# Banker_EDGE_2_DSUB.net
KiCad netlist of a schematic drawn in Altium Designer
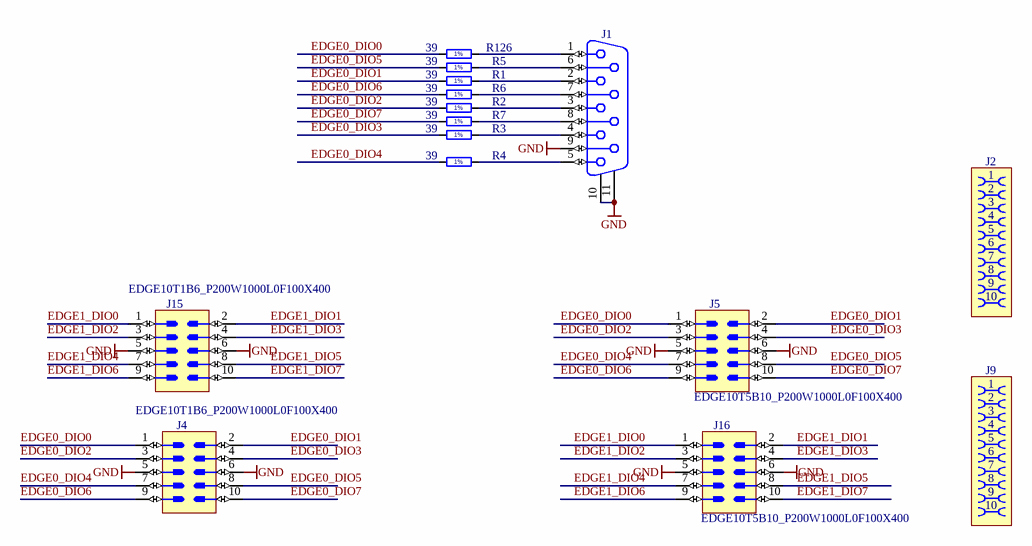
[diagram p0: Banker_EDGE_2_DSUB.SchDoc]

(export (version "E")
  (design (tool "Eeschema 10.0.6"))
  (components
    (comp (ref "J1")
      (value "D-Sub")
      (footprint "AMPHENOL_L77SDEH09SOL2RM5")
      (description "Connector D-sub 9 Female")
      (fields
        (field (name "PART NUMBER") "AMPHENOL_L77SDEH09SOL2RM5")
        (field (name "MANUFACTURER") "AMPHENOL")
        (field (name "AUTHOR") "CERN DEM JLC")
      )
      (libsource (lib "Connectors") (part "Connector D-sub 9 Female"))
    )
    (comp (ref "J2")
      (value "~")
      (footprint "AVX_00 9159 010 061 916")
      (description "Open Ended Card Edge Connector, 9159 Series")
      (fields
        (field (name "PART NUMBER") "AVX_00 9159 010 061 916")
        (field (name "MANUFACTURER") "AVX")
        (field (name "AUTHOR") "CERN DEM MR")
      )
      (libsource (lib "Connectors") (part "AVX_00 9159 010 061 916"))
    )
    (comp (ref "J4")
      (value "~")
      (footprint "EDGE10T1B6_P200W1000L0F100X400")
      (description "PCB Edge Connector 10 (2x5)")
      (fields
        (field (name "PART NUMBER") "EDGE10T1B6_P200W1000L0F100X400")
        (field (name "AUTHOR") "CERN DEM MR")
      )
      (libsource (lib "Connectors") (part "PCB Edge Connector 10 (2x5)"))
    )
    (comp (ref "J5")
      (value "~")
      (footprint "EDGE10T5B10_P200W1000L0F100X400")
      (description "PCB Edge Connector 10 (2x5)")
      (fields
        (field (name "PART NUMBER") "EDGE10T5B10_P200W1000L0F100X400")
        (field (name "AUTHOR") "CERN DEM MR")
      )
      (libsource (lib "Connectors") (part "PCB Edge Connector 10 (2x5)"))
    )
    (comp (ref "J9")
      (value "~")
      (footprint "AVX_00 9159 010 061 916")
      (description "Open Ended Card Edge Connector, 9159 Series")
      (fields
        (field (name "PART NUMBER") "AVX_00 9159 010 061 916")
        (field (name "MANUFACTURER") "AVX")
        (field (name "AUTHOR") "CERN DEM MR")
      )
      (libsource (lib "Connectors") (part "AVX_00 9159 010 061 916"))
    )
    (comp (ref "J15")
      (value "~")
      (footprint "EDGE10T1B6_P200W1000L0F100X400")
      (description "PCB Edge Connector 10 (2x5)")
      (fields
        (field (name "PART NUMBER") "EDGE10T1B6_P200W1000L0F100X400")
        (field (name "AUTHOR") "CERN DEM MR")
      )
      (libsource (lib "Connectors") (part "PCB Edge Connector 10 (2x5)"))
    )
    (comp (ref "J16")
      (value "~")
      (footprint "EDGE10T5B10_P200W1000L0F100X400")
      (description "PCB Edge Connector 10 (2x5)")
      (fields
        (field (name "PART NUMBER") "EDGE10T5B10_P200W1000L0F100X400")
        (field (name "AUTHOR") "CERN DEM MR")
      )
      (libsource (lib "Connectors") (part "PCB Edge Connector 10 (2x5)"))
    )
    (comp (ref "R1")
      (value "39")
      (footprint "RESC2012X60N")
      (description "Resistor - 1%")
      (fields
        (field (name "PART NUMBER") "R0805_39R_1%_0.125W_100PPM")
        (field (name "POWER") "0.125W")
        (field (name "AUTHOR") "CERN DEM JLC")
      )
      (libsource (lib "Resistors") (part "Resistor - 1%"))
    )
    (comp (ref "R2")
      (value "39")
      (footprint "RESC2012X60N")
      (description "Resistor - 1%")
      (fields
        (field (name "PART NUMBER") "R0805_39R_1%_0.125W_100PPM")
        (field (name "POWER") "0.125W")
        (field (name "AUTHOR") "CERN DEM JLC")
      )
      (libsource (lib "Resistors") (part "Resistor - 1%"))
    )
    (comp (ref "R3")
      (value "39")
      (footprint "RESC2012X60N")
      (description "Resistor - 1%")
      (fields
        (field (name "PART NUMBER") "R0805_39R_1%_0.125W_100PPM")
        (field (name "POWER") "0.125W")
        (field (name "AUTHOR") "CERN DEM JLC")
      )
      (libsource (lib "Resistors") (part "Resistor - 1%"))
    )
    (comp (ref "R4")
      (value "39")
      (footprint "RESC2012X60N")
      (description "Resistor - 1%")
      (fields
        (field (name "PART NUMBER") "R0805_39R_1%_0.125W_100PPM")
        (field (name "POWER") "0.125W")
        (field (name "AUTHOR") "CERN DEM JLC")
      )
      (libsource (lib "Resistors") (part "Resistor - 1%"))
    )
    (comp (ref "R5")
      (value "39")
      (footprint "RESC2012X60N")
      (description "Resistor - 1%")
      (fields
        (field (name "PART NUMBER") "R0805_39R_1%_0.125W_100PPM")
        (field (name "POWER") "0.125W")
        (field (name "AUTHOR") "CERN DEM JLC")
      )
      (libsource (lib "Resistors") (part "Resistor - 1%"))
    )
    (comp (ref "R6")
      (value "39")
      (footprint "RESC2012X60N")
      (description "Resistor - 1%")
      (fields
        (field (name "PART NUMBER") "R0805_39R_1%_0.125W_100PPM")
        (field (name "POWER") "0.125W")
        (field (name "AUTHOR") "CERN DEM JLC")
      )
      (libsource (lib "Resistors") (part "Resistor - 1%"))
    )
    (comp (ref "R7")
      (value "39")
      (footprint "RESC2012X60N")
      (description "Resistor - 1%")
      (fields
        (field (name "PART NUMBER") "R0805_39R_1%_0.125W_100PPM")
        (field (name "POWER") "0.125W")
        (field (name "AUTHOR") "CERN DEM JLC")
      )
      (libsource (lib "Resistors") (part "Resistor - 1%"))
    )
    (comp (ref "R126")
      (value "39")
      (footprint "RESC2012X60N")
      (description "Resistor - 1%")
      (fields
        (field (name "PART NUMBER") "R0805_39R_1%_0.125W_100PPM")
        (field (name "POWER") "0.125W")
        (field (name "AUTHOR") "CERN DEM JLC")
      )
      (libsource (lib "Resistors") (part "Resistor - 1%"))
    )
  )
  (nets
    (net (code "1") (name "/EDGE0_DIO0") (class "Default")
      (node (ref "J4") (pin "1") (pinfunction "1_1") (pintype "bidirectional"))
      (node (ref "J5") (pin "1") (pinfunction "1_1") (pintype "bidirectional"))
      (node (ref "R126") (pin "1") (pinfunction "1_1") (pintype "passive"))
    )
    (net (code "2") (name "/EDGE0_DIO1") (class "Default")
      (node (ref "J4") (pin "2") (pinfunction "2_2") (pintype "bidirectional"))
      (node (ref "J5") (pin "2") (pinfunction "2_2") (pintype "bidirectional"))
      (node (ref "R1") (pin "1") (pinfunction "1_1") (pintype "passive"))
    )
    (net (code "3") (name "/EDGE0_DIO2") (class "Default")
      (node (ref "J4") (pin "3") (pinfunction "3_3") (pintype "bidirectional"))
      (node (ref "J5") (pin "3") (pinfunction "3_3") (pintype "bidirectional"))
      (node (ref "R2") (pin "1") (pinfunction "1_1") (pintype "passive"))
    )
    (net (code "4") (name "/EDGE0_DIO3") (class "Default")
      (node (ref "J4") (pin "4") (pinfunction "4_4") (pintype "bidirectional"))
      (node (ref "J5") (pin "4") (pinfunction "4_4") (pintype "bidirectional"))
      (node (ref "R3") (pin "1") (pinfunction "1_1") (pintype "passive"))
    )
    (net (code "5") (name "/EDGE0_DIO4") (class "Default")
      (node (ref "J4") (pin "7") (pinfunction "7_7") (pintype "bidirectional"))
      (node (ref "J5") (pin "7") (pinfunction "7_7") (pintype "bidirectional"))
      (node (ref "R4") (pin "1") (pinfunction "1_1") (pintype "passive"))
    )
    (net (code "6") (name "/EDGE0_DIO5") (class "Default")
      (node (ref "J4") (pin "8") (pinfunction "8_8") (pintype "bidirectional"))
      (node (ref "J5") (pin "8") (pinfunction "8_8") (pintype "bidirectional"))
      (node (ref "R5") (pin "1") (pinfunction "1_1") (pintype "passive"))
    )
    (net (code "7") (name "/EDGE0_DIO6") (class "Default")
      (node (ref "J4") (pin "9") (pinfunction "9_9") (pintype "bidirectional"))
      (node (ref "J5") (pin "9") (pinfunction "9_9") (pintype "bidirectional"))
      (node (ref "R6") (pin "1") (pinfunction "1_1") (pintype "passive"))
    )
    (net (code "8") (name "/EDGE0_DIO7") (class "Default")
      (node (ref "J4") (pin "10") (pinfunction "10_10") (pintype "bidirectional"))
      (node (ref "J5") (pin "10") (pinfunction "10_10") (pintype "bidirectional"))
      (node (ref "R7") (pin "1") (pinfunction "1_1") (pintype "passive"))
    )
    (net (code "9") (name "/EDGE1_DIO0") (class "Default")
      (node (ref "J15") (pin "1") (pinfunction "1_1") (pintype "bidirectional"))
      (node (ref "J16") (pin "1") (pinfunction "1_1") (pintype "bidirectional"))
    )
    (net (code "10") (name "/EDGE1_DIO1") (class "Default")
      (node (ref "J15") (pin "2") (pinfunction "2_2") (pintype "bidirectional"))
      (node (ref "J16") (pin "2") (pinfunction "2_2") (pintype "bidirectional"))
    )
    (net (code "11") (name "/EDGE1_DIO2") (class "Default")
      (node (ref "J15") (pin "3") (pinfunction "3_3") (pintype "bidirectional"))
      (node (ref "J16") (pin "3") (pinfunction "3_3") (pintype "bidirectional"))
    )
    (net (code "12") (name "/EDGE1_DIO3") (class "Default")
      (node (ref "J15") (pin "4") (pinfunction "4_4") (pintype "bidirectional"))
      (node (ref "J16") (pin "4") (pinfunction "4_4") (pintype "bidirectional"))
    )
    (net (code "13") (name "/EDGE1_DIO4") (class "Default")
      (node (ref "J15") (pin "7") (pinfunction "7_7") (pintype "bidirectional"))
      (node (ref "J16") (pin "7") (pinfunction "7_7") (pintype "bidirectional"))
    )
    (net (code "14") (name "/EDGE1_DIO5") (class "Default")
      (node (ref "J15") (pin "8") (pinfunction "8_8") (pintype "bidirectional"))
      (node (ref "J16") (pin "8") (pinfunction "8_8") (pintype "bidirectional"))
    )
    (net (code "15") (name "/EDGE1_DIO6") (class "Default")
      (node (ref "J15") (pin "9") (pinfunction "9_9") (pintype "bidirectional"))
      (node (ref "J16") (pin "9") (pinfunction "9_9") (pintype "bidirectional"))
    )
    (net (code "16") (name "/EDGE1_DIO7") (class "Default")
      (node (ref "J15") (pin "10") (pinfunction "10_10") (pintype "bidirectional"))
      (node (ref "J16") (pin "10") (pinfunction "10_10") (pintype "bidirectional"))
    )
    (net (code "17") (name "GND") (class "Default")
      (node (ref "J1") (pin "10") (pinfunction "10_10") (pintype "passive"))
      (node (ref "J1") (pin "11") (pinfunction "11_11") (pintype "passive"))
      (node (ref "J1") (pin "9") (pinfunction "9_9") (pintype "bidirectional"))
      (node (ref "J15") (pin "5") (pinfunction "5_5") (pintype "bidirectional"))
      (node (ref "J15") (pin "6") (pinfunction "6_6") (pintype "bidirectional"))
      (node (ref "J16") (pin "5") (pinfunction "5_5") (pintype "bidirectional"))
      (node (ref "J16") (pin "6") (pinfunction "6_6") (pintype "bidirectional"))
      (node (ref "J4") (pin "5") (pinfunction "5_5") (pintype "bidirectional"))
      (node (ref "J4") (pin "6") (pinfunction "6_6") (pintype "bidirectional"))
      (node (ref "J5") (pin "5") (pinfunction "5_5") (pintype "bidirectional"))
      (node (ref "J5") (pin "6") (pinfunction "6_6") (pintype "bidirectional"))
    )
    (net (code "18") (name "Net-(J1-Pad1)") (class "Default")
      (node (ref "J1") (pin "1") (pinfunction "1_1") (pintype "bidirectional"))
      (node (ref "R126") (pin "2") (pinfunction "2_2") (pintype "passive"))
    )
    (net (code "19") (name "Net-(J1-Pad2)") (class "Default")
      (node (ref "J1") (pin "2") (pinfunction "2_2") (pintype "bidirectional"))
      (node (ref "R1") (pin "2") (pinfunction "2_2") (pintype "passive"))
    )
    (net (code "20") (name "Net-(J1-Pad3)") (class "Default")
      (node (ref "J1") (pin "3") (pinfunction "3_3") (pintype "bidirectional"))
      (node (ref "R2") (pin "2") (pinfunction "2_2") (pintype "passive"))
    )
    (net (code "21") (name "Net-(J1-Pad4)") (class "Default")
      (node (ref "J1") (pin "4") (pinfunction "4_4") (pintype "bidirectional"))
      (node (ref "R3") (pin "2") (pinfunction "2_2") (pintype "passive"))
    )
    (net (code "22") (name "Net-(J1-Pad5)") (class "Default")
      (node (ref "J1") (pin "5") (pinfunction "5_5") (pintype "bidirectional"))
      (node (ref "R4") (pin "2") (pinfunction "2_2") (pintype "passive"))
    )
    (net (code "23") (name "Net-(J1-Pad6)") (class "Default")
      (node (ref "J1") (pin "6") (pinfunction "6_6") (pintype "bidirectional"))
      (node (ref "R5") (pin "2") (pinfunction "2_2") (pintype "passive"))
    )
    (net (code "24") (name "Net-(J1-Pad7)") (class "Default")
      (node (ref "J1") (pin "7") (pinfunction "7_7") (pintype "bidirectional"))
      (node (ref "R6") (pin "2") (pinfunction "2_2") (pintype "passive"))
    )
    (net (code "25") (name "Net-(J1-Pad8)") (class "Default")
      (node (ref "J1") (pin "8") (pinfunction "8_8") (pintype "bidirectional"))
      (node (ref "R7") (pin "2") (pinfunction "2_2") (pintype "passive"))
    )
  )
)
